# Rocky_Switch.net
KiCad netlist of a schematic drawn in EAGLE
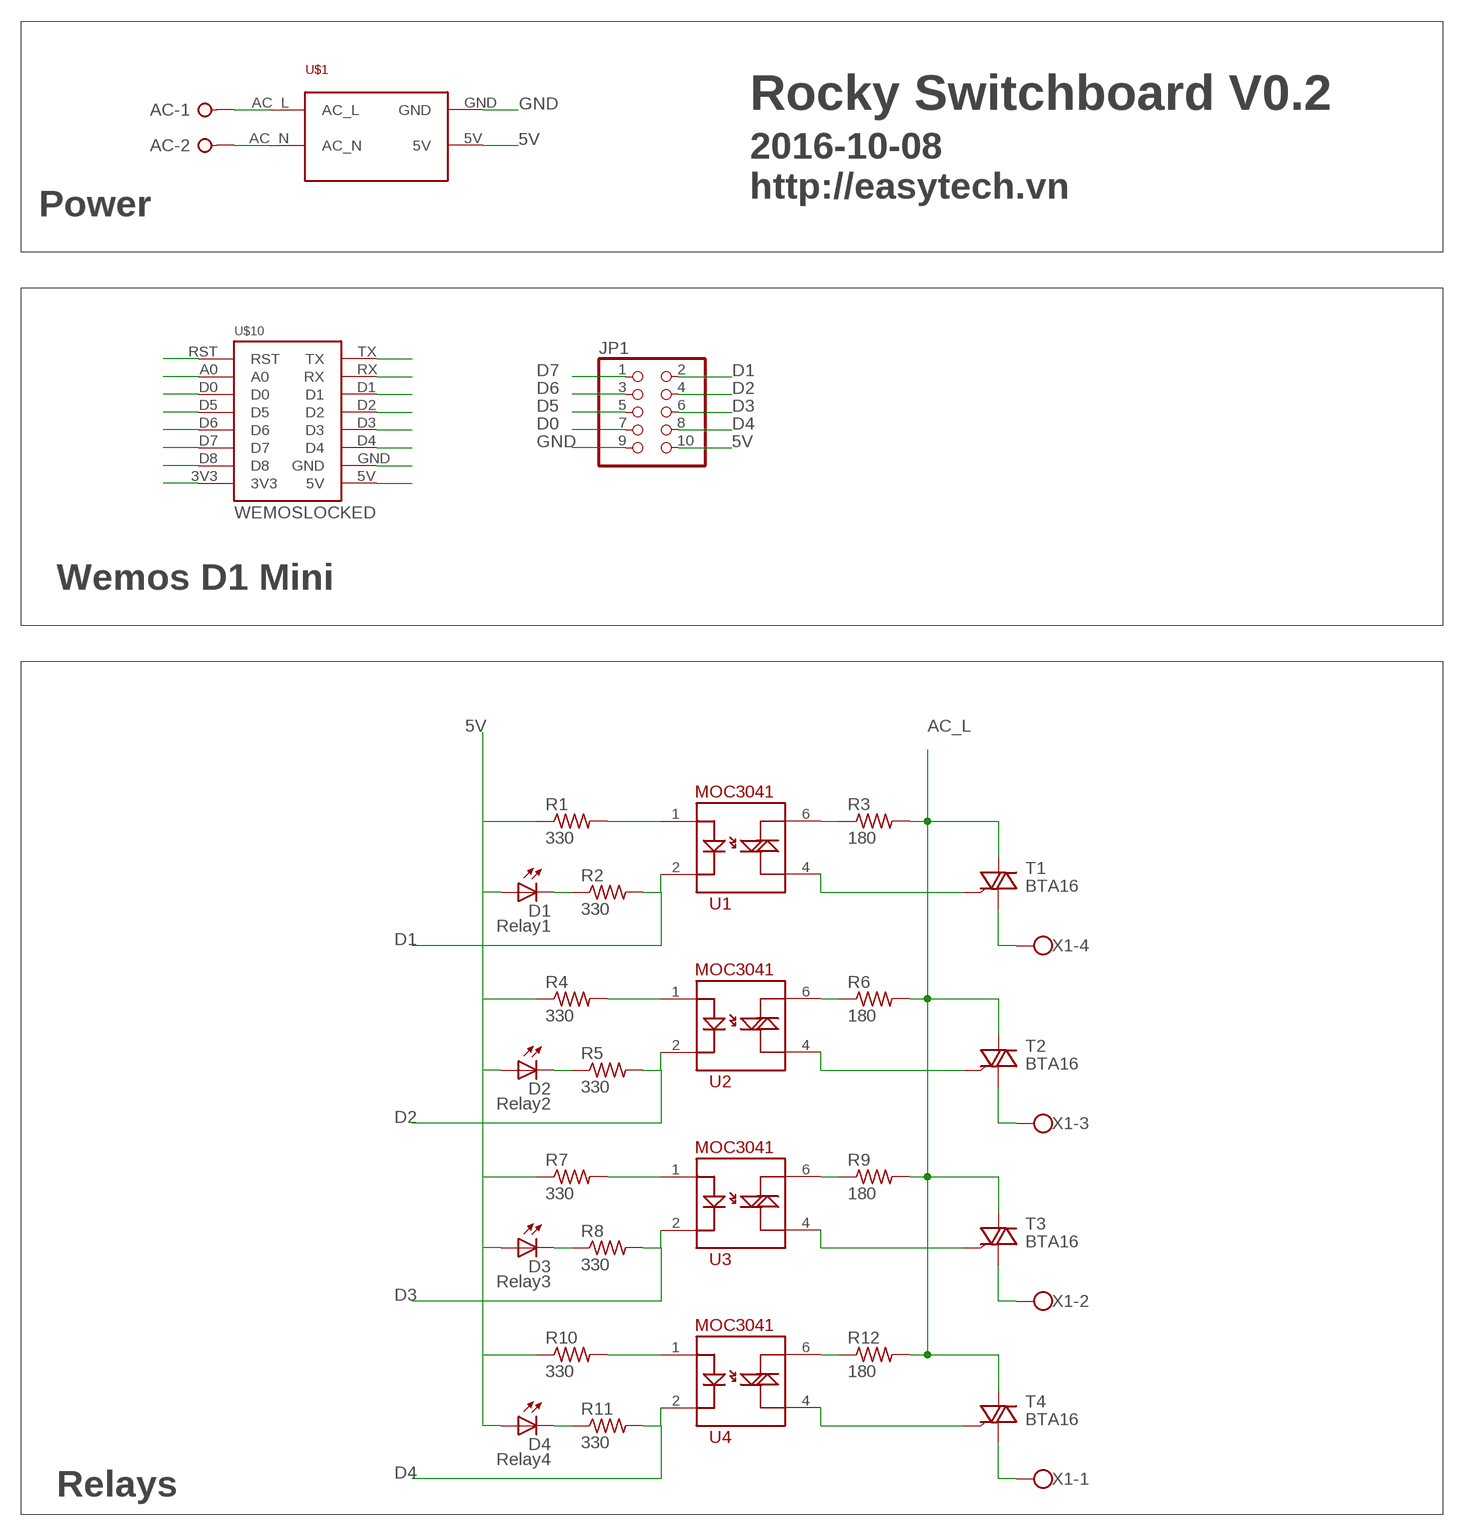
[diagram p0: schematic, sheet 1]

(export (version "E")
  (design (tool "Eeschema 10.0.6"))
  (components
    (comp (ref "AC")
      (value "W237-02P")
      (footprint "eagle-import:W237-132")
      (libsource (lib "eagle-import") (part "W237-02P"))
    )
    (comp (ref "D1")
      (value "Relay1")
      (footprint "eagle-import:CHIP-LED0805")
      (libsource (lib "eagle-import") (part "LEDCHIP-LED0805"))
    )
    (comp (ref "D2")
      (value "Relay2")
      (footprint "eagle-import:CHIP-LED0805")
      (libsource (lib "eagle-import") (part "LEDCHIP-LED0805"))
    )
    (comp (ref "D3")
      (value "Relay3")
      (footprint "eagle-import:CHIP-LED0805")
      (libsource (lib "eagle-import") (part "LEDCHIP-LED0805"))
    )
    (comp (ref "D4")
      (value "Relay4")
      (footprint "eagle-import:CHIP-LED0805")
      (libsource (lib "eagle-import") (part "LEDCHIP-LED0805"))
    )
    (comp (ref "JP1")
      (value "PINHD-2X5")
      (footprint "eagle-import:2X05")
      (libsource (lib "eagle-import") (part "PINHD-2X5"))
    )
    (comp (ref "R1")
      (value "330")
      (footprint "eagle-import:R0805")
      (libsource (lib "eagle-import") (part "R-US_R0805"))
    )
    (comp (ref "R2")
      (value "330")
      (footprint "eagle-import:R0805")
      (libsource (lib "eagle-import") (part "R-US_R0805"))
    )
    (comp (ref "R3")
      (value "180")
      (footprint "eagle-import:0204_7")
      (libsource (lib "eagle-import") (part "R-US_0204/7"))
    )
    (comp (ref "R4")
      (value "330")
      (footprint "eagle-import:R0805")
      (libsource (lib "eagle-import") (part "R-US_R0805"))
    )
    (comp (ref "R5")
      (value "330")
      (footprint "eagle-import:R0805")
      (libsource (lib "eagle-import") (part "R-US_R0805"))
    )
    (comp (ref "R6")
      (value "180")
      (footprint "eagle-import:0204_7")
      (libsource (lib "eagle-import") (part "R-US_0204/7"))
    )
    (comp (ref "R7")
      (value "330")
      (footprint "eagle-import:R0805")
      (libsource (lib "eagle-import") (part "R-US_R0805"))
    )
    (comp (ref "R8")
      (value "330")
      (footprint "eagle-import:R0805")
      (libsource (lib "eagle-import") (part "R-US_R0805"))
    )
    (comp (ref "R9")
      (value "180")
      (footprint "eagle-import:0204_7")
      (libsource (lib "eagle-import") (part "R-US_0204/7"))
    )
    (comp (ref "R10")
      (value "330")
      (footprint "eagle-import:R0805")
      (libsource (lib "eagle-import") (part "R-US_R0805"))
    )
    (comp (ref "R11")
      (value "330")
      (footprint "eagle-import:R0805")
      (libsource (lib "eagle-import") (part "R-US_R0805"))
    )
    (comp (ref "R12")
      (value "180")
      (footprint "eagle-import:0204_7")
      (libsource (lib "eagle-import") (part "R-US_0204/7"))
    )
    (comp (ref "T1")
      (value "BTA16")
      (footprint "eagle-import:TO220BV")
      (libsource (lib "eagle-import") (part "BT138-V"))
    )
    (comp (ref "T2")
      (value "BTA16")
      (footprint "eagle-import:TO220BV")
      (libsource (lib "eagle-import") (part "BT138-V"))
    )
    (comp (ref "T3")
      (value "BTA16")
      (footprint "eagle-import:TO220BV")
      (libsource (lib "eagle-import") (part "BT138-V"))
    )
    (comp (ref "T4")
      (value "BTA16")
      (footprint "eagle-import:TO220BV")
      (libsource (lib "eagle-import") (part "BT138-V"))
    )
    (comp (ref "U$1")
      (value "POWER_SUPPLY_220VAC_5V")
      (footprint "eagle-import:POWER_SUPPLY_220VAC_5V")
      (libsource (lib "eagle-import") (part "POWER_SUPPLY_220VAC_5V"))
    )
    (comp (ref "U$10")
      (value "WEMOSLOCKED")
      (footprint "eagle-import:WEMOS_LOCKED")
      (libsource (lib "eagle-import") (part "WEMOSLOCKED"))
    )
    (comp (ref "U1")
      (value "MOC3041")
      (footprint "eagle-import:DIL06")
      (libsource (lib "eagle-import") (part "MOC3031-M"))
    )
    (comp (ref "U2")
      (value "MOC3041")
      (footprint "eagle-import:DIL06")
      (libsource (lib "eagle-import") (part "MOC3031-M"))
    )
    (comp (ref "U3")
      (value "MOC3041")
      (footprint "eagle-import:DIL06")
      (libsource (lib "eagle-import") (part "MOC3031-M"))
    )
    (comp (ref "U4")
      (value "MOC3041")
      (footprint "eagle-import:DIL06")
      (libsource (lib "eagle-import") (part "MOC3031-M"))
    )
    (comp (ref "X1")
      (value "W237-4")
      (footprint "eagle-import:W237-4")
      (libsource (lib "eagle-import") (part "W237-4"))
    )
  )
  (nets
    (net (code "1") (name "/5V") (class "Default")
      (node (ref "D1") (pin "A") (pinfunction "A_A") (pintype "passive"))
      (node (ref "D2") (pin "A") (pinfunction "A_A") (pintype "passive"))
      (node (ref "D3") (pin "A") (pinfunction "A_A") (pintype "passive"))
      (node (ref "D4") (pin "A") (pinfunction "A_A") (pintype "passive"))
      (node (ref "JP1") (pin "10") (pinfunction "10_10") (pintype "passive"))
      (node (ref "R1") (pin "1") (pinfunction "1_1") (pintype "passive"))
      (node (ref "R10") (pin "1") (pinfunction "1_1") (pintype "passive"))
      (node (ref "R4") (pin "1") (pinfunction "1_1") (pintype "passive"))
      (node (ref "R7") (pin "1") (pinfunction "1_1") (pintype "passive"))
      (node (ref "U$1") (pin "5V") (pinfunction "5V_5V") (pintype "bidirectional"))
      (node (ref "U$10") (pin "5V") (pinfunction "5V_5V") (pintype "bidirectional"))
    )
    (net (code "2") (name "/AC_L") (class "Default")
      (node (ref "AC") (pin "1") (pinfunction "KL_1") (pintype "passive"))
      (node (ref "R12") (pin "2") (pinfunction "2_2") (pintype "passive"))
      (node (ref "R3") (pin "2") (pinfunction "2_2") (pintype "passive"))
      (node (ref "R6") (pin "2") (pinfunction "2_2") (pintype "passive"))
      (node (ref "R9") (pin "2") (pinfunction "2_2") (pintype "passive"))
      (node (ref "T1") (pin "T2") (pinfunction "A2_T2") (pintype "passive"))
      (node (ref "T2") (pin "T2") (pinfunction "A2_T2") (pintype "passive"))
      (node (ref "T3") (pin "T2") (pinfunction "A2_T2") (pintype "passive"))
      (node (ref "T4") (pin "T2") (pinfunction "A2_T2") (pintype "passive"))
      (node (ref "U$1") (pin "AC_L") (pinfunction "AC_L_AC_L") (pintype "bidirectional"))
    )
    (net (code "3") (name "/D0") (class "Default")
      (node (ref "JP1") (pin "7") (pinfunction "7_7") (pintype "passive"))
      (node (ref "U$10") (pin "D0") (pinfunction "D0_D0") (pintype "bidirectional"))
    )
    (net (code "4") (name "/D1") (class "Default")
      (node (ref "JP1") (pin "2") (pinfunction "2_2") (pintype "passive"))
      (node (ref "R2") (pin "2") (pinfunction "2_2") (pintype "passive"))
      (node (ref "U$10") (pin "D1") (pinfunction "D1_D1") (pintype "bidirectional"))
      (node (ref "U1") (pin "2") (pinfunction "2_2") (pintype "bidirectional"))
    )
    (net (code "5") (name "/D2") (class "Default")
      (node (ref "JP1") (pin "4") (pinfunction "4_4") (pintype "passive"))
      (node (ref "R5") (pin "2") (pinfunction "2_2") (pintype "passive"))
      (node (ref "U$10") (pin "D2") (pinfunction "D2_D2") (pintype "bidirectional"))
      (node (ref "U2") (pin "2") (pinfunction "2_2") (pintype "bidirectional"))
    )
    (net (code "6") (name "/D3") (class "Default")
      (node (ref "JP1") (pin "6") (pinfunction "6_6") (pintype "passive"))
      (node (ref "R8") (pin "2") (pinfunction "2_2") (pintype "passive"))
      (node (ref "U$10") (pin "D3") (pinfunction "D3_D3") (pintype "bidirectional"))
      (node (ref "U3") (pin "2") (pinfunction "2_2") (pintype "bidirectional"))
    )
    (net (code "7") (name "/D4") (class "Default")
      (node (ref "JP1") (pin "8") (pinfunction "8_8") (pintype "passive"))
      (node (ref "R11") (pin "2") (pinfunction "2_2") (pintype "passive"))
      (node (ref "U$10") (pin "D4") (pinfunction "D4_D4") (pintype "bidirectional"))
      (node (ref "U4") (pin "2") (pinfunction "2_2") (pintype "bidirectional"))
    )
    (net (code "8") (name "/D5") (class "Default")
      (node (ref "JP1") (pin "5") (pinfunction "5_5") (pintype "passive"))
      (node (ref "U$10") (pin "D5") (pinfunction "D5_D5") (pintype "bidirectional"))
    )
    (net (code "9") (name "/D6") (class "Default")
      (node (ref "JP1") (pin "3") (pinfunction "3_3") (pintype "passive"))
      (node (ref "U$10") (pin "D6") (pinfunction "D6_D6") (pintype "bidirectional"))
    )
    (net (code "10") (name "/D7") (class "Default")
      (node (ref "JP1") (pin "1") (pinfunction "1_1") (pintype "passive"))
      (node (ref "U$10") (pin "D7") (pinfunction "D7_D7") (pintype "bidirectional"))
    )
    (net (code "11") (name "/GND") (class "Default")
      (node (ref "JP1") (pin "9") (pinfunction "9_9") (pintype "passive"))
      (node (ref "U$1") (pin "GND") (pinfunction "GND_GND") (pintype "bidirectional"))
      (node (ref "U$10") (pin "GND") (pinfunction "GND_GND") (pintype "bidirectional"))
    )
    (net (code "12") (name "Net-(ACB-KL)") (class "Default")
      (node (ref "AC") (pin "2") (pinfunction "KL_2") (pintype "passive"))
      (node (ref "U$1") (pin "AC_N") (pinfunction "AC_N_AC_N") (pintype "bidirectional"))
    )
    (net (code "13") (name "Net-(D1-PadC)") (class "Default")
      (node (ref "D1") (pin "C") (pinfunction "C_C") (pintype "passive"))
      (node (ref "R2") (pin "1") (pinfunction "1_1") (pintype "passive"))
    )
    (net (code "14") (name "Net-(D2-PadC)") (class "Default")
      (node (ref "D2") (pin "C") (pinfunction "C_C") (pintype "passive"))
      (node (ref "R5") (pin "1") (pinfunction "1_1") (pintype "passive"))
    )
    (net (code "15") (name "Net-(D3-PadC)") (class "Default")
      (node (ref "D3") (pin "C") (pinfunction "C_C") (pintype "passive"))
      (node (ref "R8") (pin "1") (pinfunction "1_1") (pintype "passive"))
    )
    (net (code "16") (name "Net-(D4-PadC)") (class "Default")
      (node (ref "D4") (pin "C") (pinfunction "C_C") (pintype "passive"))
      (node (ref "R11") (pin "1") (pinfunction "1_1") (pintype "passive"))
    )
    (net (code "17") (name "Net-(R1-Pad2)") (class "Default")
      (node (ref "R1") (pin "2") (pinfunction "2_2") (pintype "passive"))
      (node (ref "U1") (pin "1") (pinfunction "1_1") (pintype "bidirectional"))
    )
    (net (code "18") (name "Net-(R3-Pad1)") (class "Default")
      (node (ref "R3") (pin "1") (pinfunction "1_1") (pintype "passive"))
      (node (ref "U1") (pin "6") (pinfunction "6_6") (pintype "bidirectional"))
    )
    (net (code "19") (name "Net-(R4-Pad2)") (class "Default")
      (node (ref "R4") (pin "2") (pinfunction "2_2") (pintype "passive"))
      (node (ref "U2") (pin "1") (pinfunction "1_1") (pintype "bidirectional"))
    )
    (net (code "20") (name "Net-(R6-Pad1)") (class "Default")
      (node (ref "R6") (pin "1") (pinfunction "1_1") (pintype "passive"))
      (node (ref "U2") (pin "6") (pinfunction "6_6") (pintype "bidirectional"))
    )
    (net (code "21") (name "Net-(R7-Pad2)") (class "Default")
      (node (ref "R7") (pin "2") (pinfunction "2_2") (pintype "passive"))
      (node (ref "U3") (pin "1") (pinfunction "1_1") (pintype "bidirectional"))
    )
    (net (code "22") (name "Net-(R9-Pad1)") (class "Default")
      (node (ref "R9") (pin "1") (pinfunction "1_1") (pintype "passive"))
      (node (ref "U3") (pin "6") (pinfunction "6_6") (pintype "bidirectional"))
    )
    (net (code "23") (name "Net-(R10-Pad2)") (class "Default")
      (node (ref "R10") (pin "2") (pinfunction "2_2") (pintype "passive"))
      (node (ref "U4") (pin "1") (pinfunction "1_1") (pintype "bidirectional"))
    )
    (net (code "24") (name "Net-(R12-Pad1)") (class "Default")
      (node (ref "R12") (pin "1") (pinfunction "1_1") (pintype "passive"))
      (node (ref "U4") (pin "6") (pinfunction "6_6") (pintype "bidirectional"))
    )
    (net (code "25") (name "Net-(T1-A1)") (class "Default")
      (node (ref "T1") (pin "T1") (pinfunction "A1_T1") (pintype "passive"))
      (node (ref "X1") (pin "4") (pinfunction "KL_4") (pintype "passive"))
    )
    (net (code "26") (name "Net-(T1-PadG)") (class "Default")
      (node (ref "T1") (pin "G") (pinfunction "G_G") (pintype "passive"))
      (node (ref "U1") (pin "4") (pinfunction "4_4") (pintype "bidirectional"))
    )
    (net (code "27") (name "Net-(T2-A1)") (class "Default")
      (node (ref "T2") (pin "T1") (pinfunction "A1_T1") (pintype "passive"))
      (node (ref "X1") (pin "3") (pinfunction "KL_3") (pintype "passive"))
    )
    (net (code "28") (name "Net-(T2-PadG)") (class "Default")
      (node (ref "T2") (pin "G") (pinfunction "G_G") (pintype "passive"))
      (node (ref "U2") (pin "4") (pinfunction "4_4") (pintype "bidirectional"))
    )
    (net (code "29") (name "Net-(T3-A1)") (class "Default")
      (node (ref "T3") (pin "T1") (pinfunction "A1_T1") (pintype "passive"))
      (node (ref "X1") (pin "2") (pinfunction "KL_2") (pintype "passive"))
    )
    (net (code "30") (name "Net-(T3-PadG)") (class "Default")
      (node (ref "T3") (pin "G") (pinfunction "G_G") (pintype "passive"))
      (node (ref "U3") (pin "4") (pinfunction "4_4") (pintype "bidirectional"))
    )
    (net (code "31") (name "Net-(T4-A1)") (class "Default")
      (node (ref "T4") (pin "T1") (pinfunction "A1_T1") (pintype "passive"))
      (node (ref "X1") (pin "1") (pinfunction "KL_1") (pintype "passive"))
    )
    (net (code "32") (name "Net-(T4-PadG)") (class "Default")
      (node (ref "T4") (pin "G") (pinfunction "G_G") (pintype "passive"))
      (node (ref "U4") (pin "4") (pinfunction "4_4") (pintype "bidirectional"))
    )
    (net (code "33") (name "unconnected-(U$10-Pad3V3)") (class "Default")
      (node (ref "U$10") (pin "3V3") (pinfunction "3V3_3V3") (pintype "bidirectional"))
    )
    (net (code "34") (name "unconnected-(U$10-PadA0)") (class "Default")
      (node (ref "U$10") (pin "A0") (pinfunction "A0_A0") (pintype "bidirectional"))
    )
    (net (code "35") (name "unconnected-(U$10-PadD8)") (class "Default")
      (node (ref "U$10") (pin "D8") (pinfunction "D8_D8") (pintype "bidirectional"))
    )
    (net (code "36") (name "unconnected-(U$10-PadRST)") (class "Default")
      (node (ref "U$10") (pin "RST") (pinfunction "RST_RST") (pintype "bidirectional"))
    )
    (net (code "37") (name "unconnected-(U$10-PadRX)") (class "Default")
      (node (ref "U$10") (pin "RX") (pinfunction "RX_RX") (pintype "bidirectional"))
    )
    (net (code "38") (name "unconnected-(U$10-PadTX)") (class "Default")
      (node (ref "U$10") (pin "TX") (pinfunction "TX_TX") (pintype "bidirectional"))
    )
  )
)
